# SCH.net
KiCad netlist of a schematic drawn in Altium Designer
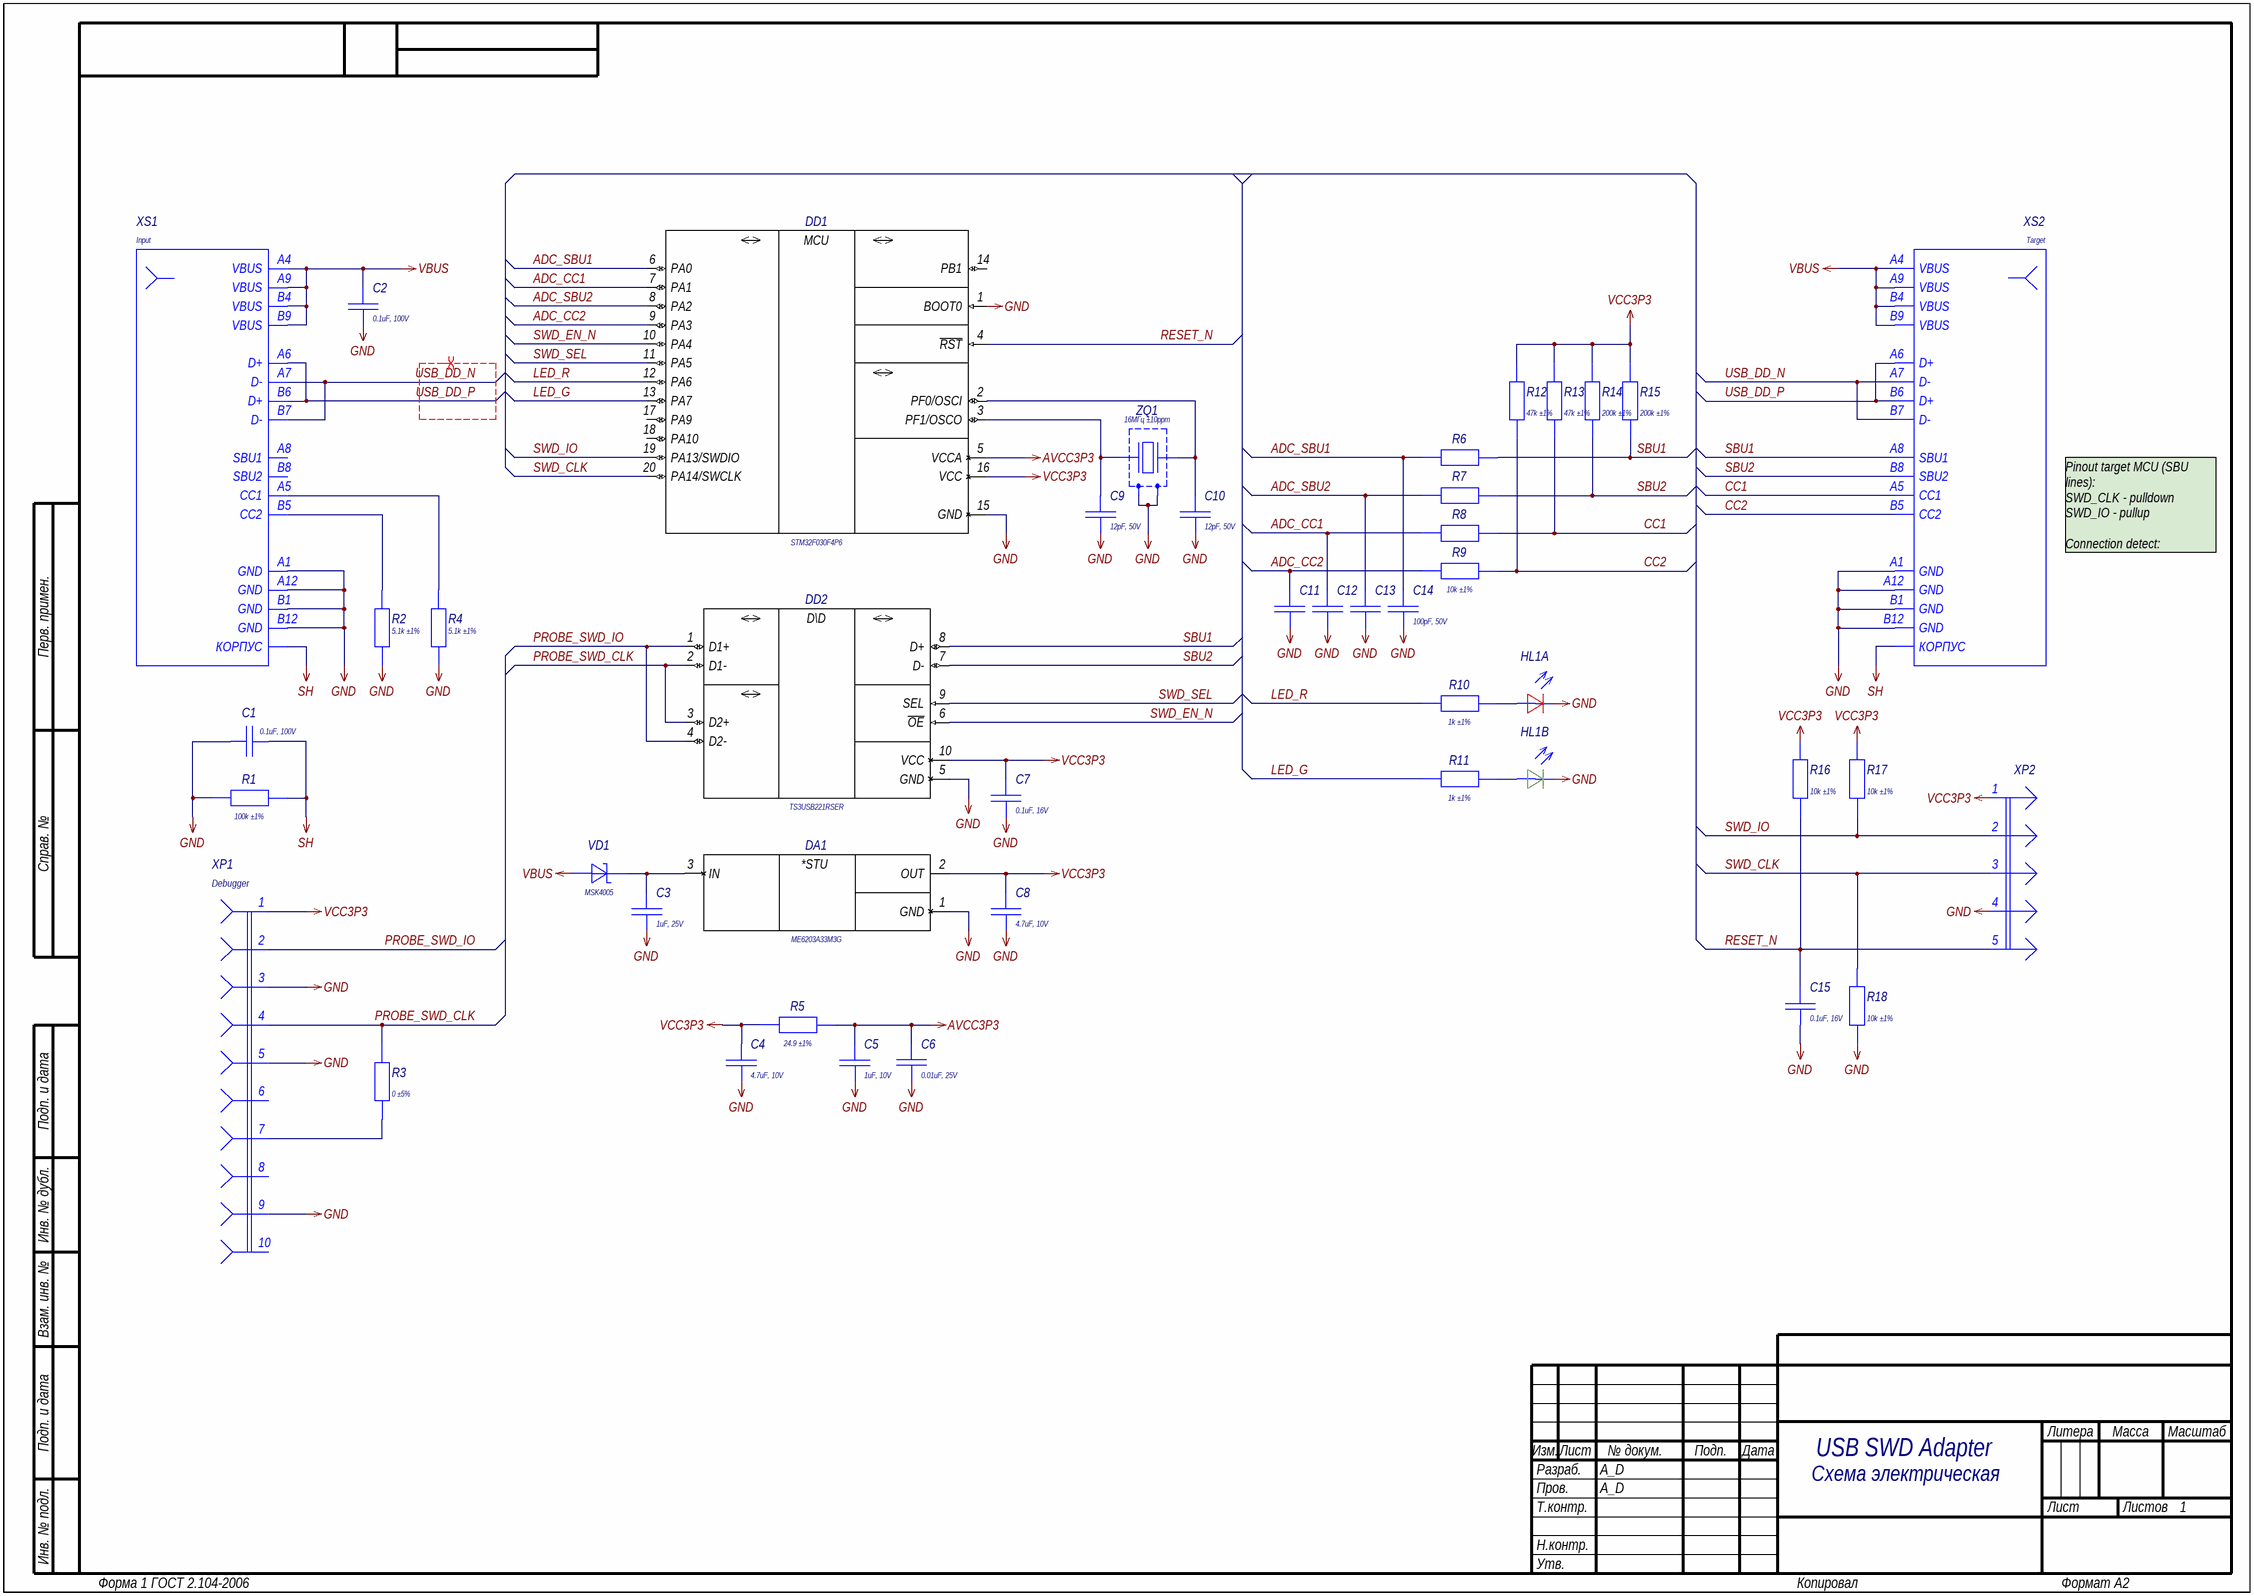
[diagram p0: SCH.SchDoc]

(export (version "E")
  (design (tool "Eeschema 10.0.6"))
  (components
    (comp (ref "C1")
      (value "Capacitor")
      (footprint "C0603_160X080H080_H")
      (fields
        (field (name "PART NUMBER") "GRM188R72A104KA35D")
        (field (name "VOLTAGE") "100V")
        (field (name "TOLERANCE") "±10%")
        (field (name "SCHEMATIC VALUE") "0.1uF, 100V")
      )
      (libsource (lib "ADLib") (part "Capacitor"))
    )
    (comp (ref "C2")
      (value "Capacitor")
      (footprint "C0603_160X080H080_H")
      (fields
        (field (name "PART NUMBER") "GRM188R72A104KA35D")
        (field (name "VOLTAGE") "100V")
        (field (name "TOLERANCE") "±10%")
        (field (name "SCHEMATIC VALUE") "0.1uF, 100V")
      )
      (libsource (lib "ADLib") (part "Capacitor"))
    )
    (comp (ref "C3")
      (value "Capacitor")
      (footprint "C0603_160X080H080_H")
      (fields
        (field (name "PART NUMBER") "GCM188R71E105KA64D")
        (field (name "VOLTAGE") "25V")
        (field (name "TOLERANCE") "±10%")
        (field (name "SCHEMATIC VALUE") "1uF, 25V")
      )
      (libsource (lib "ADLib") (part "Capacitor"))
    )
    (comp (ref "C4")
      (value "Capacitor")
      (footprint "C0402_100X050H050_H")
      (fields
        (field (name "PART NUMBER") "GRM155R61A475MEAAD")
        (field (name "VOLTAGE") "10V")
        (field (name "TOLERANCE") "±20%")
        (field (name "SCHEMATIC VALUE") "4.7uF, 10V")
      )
      (libsource (lib "ADLib") (part "Capacitor"))
    )
    (comp (ref "C5")
      (value "Capacitor")
      (footprint "C0402_100X050H050_H")
      (fields
        (field (name "PART NUMBER") "GRM155C71A105KE11D")
        (field (name "VOLTAGE") "10V")
        (field (name "TOLERANCE") "±10%")
        (field (name "SCHEMATIC VALUE") "1uF, 10V")
      )
      (libsource (lib "ADLib") (part "Capacitor"))
    )
    (comp (ref "C6")
      (value "Capacitor")
      (footprint "C0402_100X050H050_H")
      (fields
        (field (name "PART NUMBER") "GCM155R71E103KA37D")
        (field (name "VOLTAGE") "25V")
        (field (name "TOLERANCE") "±10%")
        (field (name "SCHEMATIC VALUE") "0.01uF, 25V")
      )
      (libsource (lib "ADLib") (part "Capacitor"))
    )
    (comp (ref "C7")
      (value "Capacitor")
      (footprint "C0402_100X050H050_H")
      (fields
        (field (name "PART NUMBER") "GCM155R71C104KA55D")
        (field (name "VOLTAGE") "16V")
        (field (name "TOLERANCE") "±10%")
        (field (name "SCHEMATIC VALUE") "0.1uF, 16V")
      )
      (libsource (lib "ADLib") (part "Capacitor"))
    )
    (comp (ref "C8")
      (value "Capacitor")
      (footprint "C0402_100X050H050_H")
      (fields
        (field (name "PART NUMBER") "GRM155R61A475MEAAD")
        (field (name "VOLTAGE") "10V")
        (field (name "TOLERANCE") "±20%")
        (field (name "SCHEMATIC VALUE") "4.7uF, 10V")
      )
      (libsource (lib "ADLib") (part "Capacitor"))
    )
    (comp (ref "C9")
      (value "Capacitor")
      (footprint "C0402_100X050H050_H")
      (fields
        (field (name "PART NUMBER") "GRM1555C1H120JA01D")
        (field (name "VOLTAGE") "50V")
        (field (name "TOLERANCE") "±5%")
        (field (name "SCHEMATIC VALUE") "12pF, 50V")
      )
      (libsource (lib "ADLib") (part "Capacitor"))
    )
    (comp (ref "C10")
      (value "Capacitor")
      (footprint "C0402_100X050H050_H")
      (fields
        (field (name "PART NUMBER") "GRM1555C1H120JA01D")
        (field (name "VOLTAGE") "50V")
        (field (name "TOLERANCE") "±5%")
        (field (name "SCHEMATIC VALUE") "12pF, 50V")
      )
      (libsource (lib "ADLib") (part "Capacitor"))
    )
    (comp (ref "C11")
      (value "Capacitor")
      (footprint "C0402_100X050H050_H")
      (fields
        (field (name "PART NUMBER") "GCM1555C1H101FA16D")
        (field (name "VOLTAGE") "50V")
        (field (name "TOLERANCE") "±1%")
      )
      (libsource (lib "ADLib") (part "Capacitor"))
    )
    (comp (ref "C12")
      (value "Capacitor")
      (footprint "C0402_100X050H050_H")
      (fields
        (field (name "PART NUMBER") "GCM1555C1H101FA16D")
        (field (name "VOLTAGE") "50V")
        (field (name "TOLERANCE") "±1%")
      )
      (libsource (lib "ADLib") (part "Capacitor"))
    )
    (comp (ref "C13")
      (value "Capacitor")
      (footprint "C0402_100X050H050_H")
      (fields
        (field (name "PART NUMBER") "GCM1555C1H101FA16D")
        (field (name "VOLTAGE") "50V")
        (field (name "TOLERANCE") "±1%")
      )
      (libsource (lib "ADLib") (part "Capacitor"))
    )
    (comp (ref "C14")
      (value "Capacitor")
      (footprint "C0402_100X050H050_H")
      (fields
        (field (name "PART NUMBER") "GCM1555C1H101FA16D")
        (field (name "VOLTAGE") "50V")
        (field (name "TOLERANCE") "±1%")
        (field (name "SCHEMATIC VALUE") "100pF, 50V")
      )
      (libsource (lib "ADLib") (part "Capacitor"))
    )
    (comp (ref "C15")
      (value "Capacitor")
      (footprint "C0402_100X050H050_H")
      (fields
        (field (name "PART NUMBER") "GCM155R71C104KA55D")
        (field (name "VOLTAGE") "16V")
        (field (name "TOLERANCE") "±10%")
        (field (name "SCHEMATIC VALUE") "0.1uF, 16V")
      )
      (libsource (lib "ADLib") (part "Capacitor"))
    )
    (comp (ref "DA1")
      (value "ME6203Axx-Series")
      (footprint "SOT-23_190P290X160X145_N")
      (fields
        (field (name "PART NUMBER") "ME6203A33M3G")
        (field (name "LCSC PART") "C87842")
        (field (name "MANUFACTURER") "Nanjing Micro One Elec")
        (field (name "SCHEMATIC VALUE") "ME6203A33M3G")
      )
      (libsource (lib "ADLib") (part "ME6203Axx-Series"))
    )
    (comp (ref "DD1")
      (value "STM32F030FxPx-Series")
      (footprint "TSSOP-20_065P650X440X120_N")
      (fields
        (field (name "PART NUMBER") "STM32F030F4P6")
        (field (name "LCSC PART") "C32908")
        (field (name "MANUFACTURER") "STMicroelectronics")
        (field (name "SCHEMATIC VALUE") "STM32F030F4P6")
      )
      (libsource (lib "ADLib") (part "STM32F030FxPx-Series"))
    )
    (comp (ref "DD2")
      (value "TS3USB221RSE")
      (footprint "UQFN-10_050P200X150X060_N")
      (fields
        (field (name "PART NUMBER") "TS3USB221RSER")
        (field (name "LCSC PART") "C130085")
        (field (name "MANUFACTURER") "Texas Instruments")
        (field (name "SCHEMATIC VALUE") "TS3USB221RSER")
      )
      (libsource (lib "ADLib") (part "TS3USB221RSE"))
    )
    (comp (ref "HL1")
      (value "Text")
      (footprint "LD3025")
      (fields
        (field (name "PART NUMBER") "XL-3227SURUGC")
        (field (name "LCSC PART") "C965842")
        (field (name "MANUFACTURER") "XINGLIGHT")
        (field (name "PUBLISHER") "Andrew Danich")
      )
      (libsource (lib "ADLib") (part "Led-2-RG-4p"))
    )
    (comp (ref "R1")
      (value "Resistor")
      (footprint "R0402_100X050H035_H")
      (fields
        (field (name "PART NUMBER") "0402WGF1003TCE")
        (field (name "TOLERANCE") "±1%")
        (field (name "MANUFACTURER") "Uniroyal Elec")
        (field (name "SCHEMATIC VALUE") "100k ±1%")
      )
      (libsource (lib "ADLib") (part "Resistor"))
    )
    (comp (ref "R2")
      (value "Resistor")
      (footprint "R0402_100X050H035_H")
      (fields
        (field (name "PART NUMBER") "0402WGF5101TCE")
        (field (name "TOLERANCE") "±1%")
        (field (name "MANUFACTURER") "Uniroyal Elec")
        (field (name "SCHEMATIC VALUE") "5.1k ±1%")
      )
      (libsource (lib "ADLib") (part "Resistor"))
    )
    (comp (ref "R3")
      (value "Resistor")
      (footprint "R0402_100X050H035_H")
      (fields
        (field (name "PART NUMBER") "RC0402JR-070RL")
        (field (name "TOLERANCE") "±5%")
        (field (name "MANUFACTURER") "Yageo")
        (field (name "SCHEMATIC VALUE") "0 ±5%")
      )
      (libsource (lib "ADLib") (part "Resistor"))
    )
    (comp (ref "R4")
      (value "Resistor")
      (footprint "R0402_100X050H035_H")
      (fields
        (field (name "PART NUMBER") "0402WGF5101TCE")
        (field (name "TOLERANCE") "±1%")
        (field (name "MANUFACTURER") "Uniroyal Elec")
        (field (name "SCHEMATIC VALUE") "5.1k ±1%")
      )
      (libsource (lib "ADLib") (part "Resistor"))
    )
    (comp (ref "R5")
      (value "Resistor")
      (footprint "R0402_100X050H035_H")
      (fields
        (field (name "PART NUMBER") "RC0402FR-0724R9L")
        (field (name "TOLERANCE") "±1%")
        (field (name "MANUFACTURER") "Yageo")
        (field (name "SCHEMATIC VALUE") "24.9 ±1%")
      )
      (libsource (lib "ADLib") (part "Resistor"))
    )
    (comp (ref "R6")
      (value "Resistor")
      (footprint "R0402_100X050H035_H")
      (fields
        (field (name "PART NUMBER") "0402WGF1002TCE")
        (field (name "TOLERANCE") "±1%")
        (field (name "MANUFACTURER") "Uniroyal Elec")
      )
      (libsource (lib "ADLib") (part "Resistor"))
    )
    (comp (ref "R7")
      (value "Resistor")
      (footprint "R0402_100X050H035_H")
      (fields
        (field (name "PART NUMBER") "0402WGF1002TCE")
        (field (name "TOLERANCE") "±1%")
        (field (name "MANUFACTURER") "Uniroyal Elec")
      )
      (libsource (lib "ADLib") (part "Resistor"))
    )
    (comp (ref "R8")
      (value "Resistor")
      (footprint "R0402_100X050H035_H")
      (fields
        (field (name "PART NUMBER") "0402WGF1002TCE")
        (field (name "TOLERANCE") "±1%")
        (field (name "MANUFACTURER") "Uniroyal Elec")
      )
      (libsource (lib "ADLib") (part "Resistor"))
    )
    (comp (ref "R9")
      (value "Resistor")
      (footprint "R0402_100X050H035_H")
      (fields
        (field (name "PART NUMBER") "0402WGF1002TCE")
        (field (name "TOLERANCE") "±1%")
        (field (name "MANUFACTURER") "Uniroyal Elec")
        (field (name "SCHEMATIC VALUE") "10k ±1%")
      )
      (libsource (lib "ADLib") (part "Resistor"))
    )
    (comp (ref "R10")
      (value "Resistor")
      (footprint "R0402_100X050H035_H")
      (fields
        (field (name "PART NUMBER") "0402WGF1001TCE")
        (field (name "TOLERANCE") "±1%")
        (field (name "MANUFACTURER") "Uniroyal Elec")
        (field (name "SCHEMATIC VALUE") "1k ±1%")
      )
      (libsource (lib "ADLib") (part "Resistor"))
    )
    (comp (ref "R11")
      (value "Resistor")
      (footprint "R0402_100X050H035_H")
      (fields
        (field (name "PART NUMBER") "0402WGF1001TCE")
        (field (name "TOLERANCE") "±1%")
        (field (name "MANUFACTURER") "Uniroyal Elec")
        (field (name "SCHEMATIC VALUE") "1k ±1%")
      )
      (libsource (lib "ADLib") (part "Resistor"))
    )
    (comp (ref "R12")
      (value "Resistor")
      (footprint "R0402_100X050H035_H")
      (fields
        (field (name "PART NUMBER") "0402WGF4702TCE")
        (field (name "TOLERANCE") "±1%")
        (field (name "MANUFACTURER") "Uniroyal Elec")
        (field (name "SCHEMATIC VALUE") "47k ±1%")
      )
      (libsource (lib "ADLib") (part "Resistor"))
    )
    (comp (ref "R13")
      (value "Resistor")
      (footprint "R0402_100X050H035_H")
      (fields
        (field (name "PART NUMBER") "0402WGF4702TCE")
        (field (name "TOLERANCE") "±1%")
        (field (name "MANUFACTURER") "Uniroyal Elec")
        (field (name "SCHEMATIC VALUE") "47k ±1%")
      )
      (libsource (lib "ADLib") (part "Resistor"))
    )
    (comp (ref "R14")
      (value "Resistor")
      (footprint "R0402_100X050H035_H")
      (fields
        (field (name "PART NUMBER") "0402WGF2003TCE")
        (field (name "TOLERANCE") "±1%")
        (field (name "MANUFACTURER") "Uniroyal Elec")
        (field (name "SCHEMATIC VALUE") "200k ±1%")
      )
      (libsource (lib "ADLib") (part "Resistor"))
    )
    (comp (ref "R15")
      (value "Resistor")
      (footprint "R0402_100X050H035_H")
      (fields
        (field (name "PART NUMBER") "0402WGF2003TCE")
        (field (name "TOLERANCE") "±1%")
        (field (name "MANUFACTURER") "Uniroyal Elec")
        (field (name "SCHEMATIC VALUE") "200k ±1%")
      )
      (libsource (lib "ADLib") (part "Resistor"))
    )
    (comp (ref "R16")
      (value "Resistor")
      (footprint "R0402_100X050H035_H")
      (fields
        (field (name "PART NUMBER") "0402WGF1002TCE")
        (field (name "TOLERANCE") "±1%")
        (field (name "MANUFACTURER") "Uniroyal Elec")
        (field (name "SCHEMATIC VALUE") "10k ±1%")
      )
      (libsource (lib "ADLib") (part "Resistor"))
    )
    (comp (ref "R17")
      (value "Resistor")
      (footprint "R0402_100X050H035_H")
      (fields
        (field (name "PART NUMBER") "0402WGF1002TCE")
        (field (name "TOLERANCE") "±1%")
        (field (name "MANUFACTURER") "Uniroyal Elec")
        (field (name "SCHEMATIC VALUE") "10k ±1%")
      )
      (libsource (lib "ADLib") (part "Resistor"))
    )
    (comp (ref "R18")
      (value "Resistor")
      (footprint "R0402_100X050H035_H")
      (fields
        (field (name "PART NUMBER") "0402WGF1002TCE")
        (field (name "TOLERANCE") "±1%")
        (field (name "MANUFACTURER") "Uniroyal Elec")
        (field (name "SCHEMATIC VALUE") "10k ±1%")
      )
      (libsource (lib "ADLib") (part "Resistor"))
    )
    (comp (ref "VD1")
      (value "Schottky")
      (footprint "SOD-523")
      (fields
        (field (name "PART NUMBER") "MSK4005")
        (field (name "LCSC PART") "C345957")
        (field (name "MANUFACTURER") "Shikues")
        (field (name "SCHEMATIC VALUE") "MSK4005")
      )
      (libsource (lib "ADLib") (part "Schottky"))
    )
    (comp (ref "XP1")
      (value "Debugger")
      (footprint "PBD-10")
      (fields (field (name "PART NUMBER") "PBD-10"))
      (libsource (lib "ADLib") (part "Con-10-F"))
    )
    (comp (ref "XP2")
      (value "SWD")
      (footprint "PLS-5")
      (fields (field (name "PART NUMBER") "PLS-5"))
      (libsource (lib "ADLib") (part "Con-5-M"))
    )
    (comp (ref "XS1")
      (value "Input")
      (footprint "U262-161N-4BVC11")
      (fields
        (field (name "PART NUMBER") "U262-161N-4BVC11")
        (field (name "LCSC PART") "C319148")
        (field (name "MANUFACTURER") "XKB Enterprise")
      )
      (libsource (lib "") (part "Con-USB_C-F-16P_1"))
    )
    (comp (ref "XS2")
      (value "Target")
      (footprint "U262-161N-4BVC11")
      (fields
        (field (name "PART NUMBER") "U262-161N-4BVC11")
        (field (name "LCSC PART") "C319148")
        (field (name "MANUFACTURER") "XKB Enterprise")
      )
      (libsource (lib "ADLib") (part "Con-USB_C-F-16P"))
    )
    (comp (ref "ZQ1")
      (value "Crystal-1_3p_S")
      (footprint "SMD 3.2x2.5mm")
      (fields
        (field (name "PART NUMBER") "X322516MOB4SI")
        (field (name "LCSC PART") "C12668")
        (field (name "MANUFACTURER") "Yangxing Tech")
        (field (name "SCHEMATIC VALUE") "16МГц ±10ppm")
      )
      (libsource (lib "ADLib") (part "Crystal-1_3p_S"))
    )
  )
  (nets
    (net (code "1") (name "/ADC_CC1") (class "Default")
      (node (ref "C12") (pin "2") (pinfunction "2_2") (pintype "passive"))
      (node (ref "DD1") (pin "7") (pinfunction "PA1_7") (pintype "bidirectional"))
      (node (ref "R8") (pin "2") (pinfunction "2_2") (pintype "passive"))
    )
    (net (code "2") (name "/ADC_CC2") (class "Default")
      (node (ref "C11") (pin "2") (pinfunction "2_2") (pintype "passive"))
      (node (ref "DD1") (pin "9") (pinfunction "PA3_9") (pintype "bidirectional"))
      (node (ref "R9") (pin "2") (pinfunction "2_2") (pintype "passive"))
    )
    (net (code "3") (name "/ADC_SBU1") (class "Default")
      (node (ref "C14") (pin "2") (pinfunction "2_2") (pintype "passive"))
      (node (ref "DD1") (pin "6") (pinfunction "PA0_6") (pintype "bidirectional"))
      (node (ref "R6") (pin "2") (pinfunction "2_2") (pintype "passive"))
    )
    (net (code "4") (name "/ADC_SBU2") (class "Default")
      (node (ref "C13") (pin "2") (pinfunction "2_2") (pintype "passive"))
      (node (ref "DD1") (pin "8") (pinfunction "PA2_8") (pintype "bidirectional"))
      (node (ref "R7") (pin "2") (pinfunction "2_2") (pintype "passive"))
    )
    (net (code "5") (name "/CC1") (class "Default")
      (node (ref "R13") (pin "1") (pinfunction "1_1") (pintype "passive"))
      (node (ref "R8") (pin "1") (pinfunction "1_1") (pintype "passive"))
      (node (ref "XS2") (pin "A5") (pinfunction "CC1_A5") (pintype "passive"))
    )
    (net (code "6") (name "/CC2") (class "Default")
      (node (ref "R12") (pin "1") (pinfunction "1_1") (pintype "passive"))
      (node (ref "R9") (pin "1") (pinfunction "1_1") (pintype "passive"))
      (node (ref "XS2") (pin "B5") (pinfunction "CC2_B5") (pintype "passive"))
    )
    (net (code "7") (name "/LED_G") (class "Default")
      (node (ref "DD1") (pin "13") (pinfunction "PA7_13") (pintype "bidirectional"))
      (node (ref "R11") (pin "2") (pinfunction "2_2") (pintype "passive"))
    )
    (net (code "8") (name "/LED_R") (class "Default")
      (node (ref "DD1") (pin "12") (pinfunction "PA6_12") (pintype "bidirectional"))
      (node (ref "R10") (pin "2") (pinfunction "2_2") (pintype "passive"))
    )
    (net (code "9") (name "/PROBE_SWD_CLK") (class "Default")
      (node (ref "DD2") (pin "2") (pinfunction "D1-_2") (pintype "bidirectional"))
      (node (ref "DD2") (pin "3") (pinfunction "D2+_3") (pintype "bidirectional"))
      (node (ref "R3") (pin "1") (pinfunction "1_1") (pintype "passive"))
      (node (ref "XP1") (pin "4") (pintype "passive"))
    )
    (net (code "10") (name "/PROBE_SWD_IO") (class "Default")
      (node (ref "DD2") (pin "1") (pinfunction "D1+_1") (pintype "bidirectional"))
      (node (ref "DD2") (pin "4") (pinfunction "D2-_4") (pintype "bidirectional"))
      (node (ref "XP1") (pin "2") (pintype "passive"))
    )
    (net (code "11") (name "/RESET_N") (class "Default")
      (node (ref "C15") (pin "2") (pinfunction "2_2") (pintype "passive"))
      (node (ref "DD1") (pin "4") (pinfunction "~{RST}_4") (pintype "input"))
      (node (ref "R16") (pin "2") (pinfunction "2_2") (pintype "passive"))
      (node (ref "XP2") (pin "5") (pintype "passive"))
    )
    (net (code "12") (name "/SBU1") (class "Default")
      (node (ref "DD2") (pin "8") (pinfunction "D+_8") (pintype "bidirectional"))
      (node (ref "R15") (pin "1") (pinfunction "1_1") (pintype "passive"))
      (node (ref "R6") (pin "1") (pinfunction "1_1") (pintype "passive"))
      (node (ref "XS2") (pin "A8") (pinfunction "SBU1_A8") (pintype "passive"))
    )
    (net (code "13") (name "/SBU2") (class "Default")
      (node (ref "DD2") (pin "7") (pinfunction "D-_7") (pintype "bidirectional"))
      (node (ref "R14") (pin "1") (pinfunction "1_1") (pintype "passive"))
      (node (ref "R7") (pin "1") (pinfunction "1_1") (pintype "passive"))
      (node (ref "XS2") (pin "B8") (pinfunction "SBU2_B8") (pintype "passive"))
    )
    (net (code "14") (name "/SWD_CLK") (class "Default")
      (node (ref "DD1") (pin "20") (pinfunction "PA14/SWCLK_20") (pintype "bidirectional"))
      (node (ref "R18") (pin "1") (pinfunction "1_1") (pintype "passive"))
      (node (ref "XP2") (pin "3") (pintype "passive"))
    )
    (net (code "15") (name "/SWD_EN_N") (class "Default")
      (node (ref "DD1") (pin "10") (pinfunction "PA4_10") (pintype "bidirectional"))
      (node (ref "DD2") (pin "6") (pinfunction "~{OE}_6") (pintype "input"))
    )
    (net (code "16") (name "/SWD_IO") (class "Default")
      (node (ref "DD1") (pin "19") (pinfunction "PA13/SWDIO_19") (pintype "bidirectional"))
      (node (ref "R17") (pin "2") (pinfunction "2_2") (pintype "passive"))
      (node (ref "XP2") (pin "2") (pintype "passive"))
    )
    (net (code "17") (name "/SWD_SEL") (class "Default")
      (node (ref "DD1") (pin "11") (pinfunction "PA5_11") (pintype "bidirectional"))
      (node (ref "DD2") (pin "9") (pinfunction "SEL_9") (pintype "input"))
    )
    (net (code "18") (name "/USB_DD_N") (class "Default")
      (node (ref "XS1") (pin "A7") (pinfunction "D-_A7") (pintype "passive"))
      (node (ref "XS1") (pin "B7") (pinfunction "D-_B7") (pintype "passive"))
      (node (ref "XS2") (pin "A7") (pinfunction "D-_A7") (pintype "passive"))
      (node (ref "XS2") (pin "B7") (pinfunction "D-_B7") (pintype "passive"))
    )
    (net (code "19") (name "/USB_DD_P") (class "Default")
      (node (ref "XS1") (pin "A6") (pinfunction "D+_A6") (pintype "passive"))
      (node (ref "XS1") (pin "B6") (pinfunction "D+_B6") (pintype "passive"))
      (node (ref "XS2") (pin "A6") (pinfunction "D+_A6") (pintype "passive"))
      (node (ref "XS2") (pin "B6") (pinfunction "D+_B6") (pintype "passive"))
    )
    (net (code "20") (name "AVCC3P3") (class "Default")
      (node (ref "C5") (pin "2") (pinfunction "2_2") (pintype "passive"))
      (node (ref "C6") (pin "1") (pinfunction "1_1") (pintype "passive"))
      (node (ref "DD1") (pin "5") (pinfunction "VCCA_5") (pintype "power_in"))
      (node (ref "R5") (pin "1") (pinfunction "1_1") (pintype "passive"))
    )
    (net (code "21") (name "GND") (class "Default")
      (node (ref "C1") (pin "2") (pinfunction "2_2") (pintype "passive"))
      (node (ref "C10") (pin "1") (pinfunction "1_1") (pintype "passive"))
      (node (ref "C11") (pin "1") (pinfunction "1_1") (pintype "passive"))
      (node (ref "C12") (pin "1") (pinfunction "1_1") (pintype "passive"))
      (node (ref "C13") (pin "1") (pinfunction "1_1") (pintype "passive"))
      (node (ref "C14") (pin "1") (pinfunction "1_1") (pintype "passive"))
      (node (ref "C15") (pin "1") (pinfunction "1_1") (pintype "passive"))
      (node (ref "C2") (pin "1") (pinfunction "1_1") (pintype "passive"))
      (node (ref "C3") (pin "1") (pinfunction "1_1") (pintype "passive"))
      (node (ref "C4") (pin "1") (pinfunction "1_1") (pintype "passive"))
      (node (ref "C5") (pin "1") (pinfunction "1_1") (pintype "passive"))
      (node (ref "C6") (pin "2") (pinfunction "2_2") (pintype "passive"))
      (node (ref "C7") (pin "1") (pinfunction "1_1") (pintype "passive"))
      (node (ref "C8") (pin "1") (pinfunction "1_1") (pintype "passive"))
      (node (ref "C9") (pin "1") (pinfunction "1_1") (pintype "passive"))
      (node (ref "DA1") (pin "1") (pinfunction "GND_1") (pintype "power_in"))
      (node (ref "DD1") (pin "1") (pinfunction "BOOT0_1") (pintype "input"))
      (node (ref "DD1") (pin "15") (pinfunction "GND_15") (pintype "power_in"))
      (node (ref "DD2") (pin "5") (pinfunction "GND_5") (pintype "power_in"))
      (node (ref "HL1") (pin "2") (pintype "passive"))
      (node (ref "HL1") (pin "4") (pintype "passive"))
      (node (ref "R1") (pin "2") (pinfunction "2_2") (pintype "passive"))
      (node (ref "R18") (pin "2") (pinfunction "2_2") (pintype "passive"))
      (node (ref "R2") (pin "1") (pinfunction "1_1") (pintype "passive"))
      (node (ref "R4") (pin "1") (pinfunction "1_1") (pintype "passive"))
      (node (ref "XP1") (pin "3") (pintype "passive"))
      (node (ref "XP1") (pin "5") (pintype "passive"))
      (node (ref "XP1") (pin "9") (pintype "passive"))
      (node (ref "XP2") (pin "4") (pintype "passive"))
      (node (ref "XS1") (pin "A1") (pinfunction "GND_A1") (pintype "passive"))
      (node (ref "XS1") (pin "A12") (pinfunction "GND_A12") (pintype "passive"))
      (node (ref "XS1") (pin "B1") (pinfunction "GND_B1") (pintype "passive"))
      (node (ref "XS1") (pin "B12") (pinfunction "GND_B12") (pintype "passive"))
      (node (ref "XS2") (pin "A1") (pinfunction "GND_A1") (pintype "passive"))
      (node (ref "XS2") (pin "A12") (pinfunction "GND_A12") (pintype "passive"))
      (node (ref "XS2") (pin "B1") (pinfunction "GND_B1") (pintype "passive"))
      (node (ref "XS2") (pin "B12") (pinfunction "GND_B12") (pintype "passive"))
      (node (ref "ZQ1") (pin "2") (pinfunction "2_2") (pintype "passive"))
      (node (ref "ZQ1") (pin "4") (pinfunction "4_4") (pintype "passive"))
    )
    (net (code "22") (name "Net-(DA1-IN)") (class "Default")
      (node (ref "C3") (pin "2") (pinfunction "2_2") (pintype "passive"))
      (node (ref "DA1") (pin "3") (pinfunction "IN_3") (pintype "power_in"))
      (node (ref "VD1") (pin "2") (pinfunction "К_2") (pintype "passive"))
    )
    (net (code "23") (name "Net-(DD1-PF0{slash}OSCI)") (class "Default")
      (node (ref "C10") (pin "2") (pinfunction "2_2") (pintype "passive"))
      (node (ref "DD1") (pin "2") (pinfunction "PF0/OSCI_2") (pintype "bidirectional"))
      (node (ref "ZQ1") (pin "3") (pinfunction "3_3") (pintype "passive"))
    )
    (net (code "24") (name "Net-(DD1-PF1{slash}OSCO)") (class "Default")
      (node (ref "C9") (pin "2") (pinfunction "2_2") (pintype "passive"))
      (node (ref "DD1") (pin "3") (pinfunction "PF1/OSCO_3") (pintype "bidirectional"))
      (node (ref "ZQ1") (pin "1") (pinfunction "1_1") (pintype "passive"))
    )
    (net (code "25") (name "Net-(HL1-Pad1)") (class "Default")
      (node (ref "HL1") (pin "1") (pintype "passive"))
      (node (ref "R10") (pin "1") (pinfunction "1_1") (pintype "passive"))
    )
    (net (code "26") (name "Net-(HL1-Pad3)") (class "Default")
      (node (ref "HL1") (pin "3") (pintype "passive"))
      (node (ref "R11") (pin "1") (pinfunction "1_1") (pintype "passive"))
    )
    (net (code "27") (name "Net-(R3-Pad2)") (class "Default")
      (node (ref "R3") (pin "2") (pinfunction "2_2") (pintype "passive"))
      (node (ref "XP1") (pin "7") (pintype "passive"))
    )
    (net (code "28") (name "Net-(XS1-CC1)") (class "Default")
      (node (ref "R4") (pin "2") (pinfunction "2_2") (pintype "passive"))
      (node (ref "XS1") (pin "A5") (pinfunction "CC1_A5") (pintype "passive"))
    )
    (net (code "29") (name "Net-(XS1-CC2)") (class "Default")
      (node (ref "R2") (pin "2") (pinfunction "2_2") (pintype "passive"))
      (node (ref "XS1") (pin "B5") (pinfunction "CC2_B5") (pintype "passive"))
    )
    (net (code "30") (name "SH") (class "Default")
      (node (ref "C1") (pin "1") (pinfunction "1_1") (pintype "passive"))
      (node (ref "R1") (pin "1") (pinfunction "1_1") (pintype "passive"))
      (node (ref "XS1") (pin "SH") (pinfunction "КОРПУС_SH") (pintype "passive"))
      (node (ref "XS2") (pin "SH") (pinfunction "КОРПУС_SH") (pintype "passive"))
    )
    (net (code "31") (name "VBUS") (class "Default")
      (node (ref "C2") (pin "2") (pinfunction "2_2") (pintype "passive"))
      (node (ref "VD1") (pin "1") (pinfunction "А_1") (pintype "passive"))
      (node (ref "XS1") (pin "A4") (pinfunction "VBUS_A4") (pintype "passive"))
      (node (ref "XS1") (pin "A9") (pinfunction "VBUS_A9") (pintype "passive"))
      (node (ref "XS1") (pin "B4") (pinfunction "VBUS_B4") (pintype "passive"))
      (node (ref "XS1") (pin "B9") (pinfunction "VBUS_B9") (pintype "passive"))
      (node (ref "XS2") (pin "A4") (pinfunction "VBUS_A4") (pintype "passive"))
      (node (ref "XS2") (pin "A9") (pinfunction "VBUS_A9") (pintype "passive"))
      (node (ref "XS2") (pin "B4") (pinfunction "VBUS_B4") (pintype "passive"))
      (node (ref "XS2") (pin "B9") (pinfunction "VBUS_B9") (pintype "passive"))
    )
    (net (code "32") (name "VCC3P3") (class "Default")
      (node (ref "C4") (pin "2") (pinfunction "2_2") (pintype "passive"))
      (node (ref "C7") (pin "2") (pinfunction "2_2") (pintype "passive"))
      (node (ref "C8") (pin "2") (pinfunction "2_2") (pintype "passive"))
      (node (ref "DA1") (pin "2") (pinfunction "OUT_2") (pintype "power_in"))
      (node (ref "DD1") (pin "16") (pinfunction "VCC_16") (pintype "power_in"))
      (node (ref "DD2") (pin "10") (pinfunction "VCC_10") (pintype "power_in"))
      (node (ref "R12") (pin "2") (pinfunction "2_2") (pintype "passive"))
      (node (ref "R13") (pin "2") (pinfunction "2_2") (pintype "passive"))
      (node (ref "R14") (pin "2") (pinfunction "2_2") (pintype "passive"))
      (node (ref "R15") (pin "2") (pinfunction "2_2") (pintype "passive"))
      (node (ref "R16") (pin "1") (pinfunction "1_1") (pintype "passive"))
      (node (ref "R17") (pin "1") (pinfunction "1_1") (pintype "passive"))
      (node (ref "R5") (pin "2") (pinfunction "2_2") (pintype "passive"))
      (node (ref "XP1") (pin "1") (pintype "passive"))
      (node (ref "XP2") (pin "1") (pintype "passive"))
    )
    (net (code "33") (name "unconnected-(DD1-PA9-Pad17)") (class "Default")
      (node (ref "DD1") (pin "17") (pinfunction "PA9_17") (pintype "bidirectional"))
    )
    (net (code "34") (name "unconnected-(DD1-PA10-Pad18)") (class "Default")
      (node (ref "DD1") (pin "18") (pinfunction "PA10_18") (pintype "bidirectional"))
    )
    (net (code "35") (name "unconnected-(DD1-PB1-Pad14)") (class "Default")
      (node (ref "DD1") (pin "14") (pinfunction "PB1_14") (pintype "bidirectional"))
    )
    (net (code "36") (name "unconnected-(XP1-Pad6)") (class "Default")
      (node (ref "XP1") (pin "6") (pintype "passive"))
    )
    (net (code "37") (name "unconnected-(XP1-Pad8)") (class "Default")
      (node (ref "XP1") (pin "8") (pintype "passive"))
    )
    (net (code "38") (name "unconnected-(XP1-Pad10)") (class "Default")
      (node (ref "XP1") (pin "10") (pintype "passive"))
    )
    (net (code "39") (name "unconnected-(XS1-SBU1-PadA8)") (class "Default")
      (node (ref "XS1") (pin "A8") (pinfunction "SBU1_A8") (pintype "passive"))
    )
    (net (code "40") (name "unconnected-(XS1-SBU2-PadB8)") (class "Default")
      (node (ref "XS1") (pin "B8") (pinfunction "SBU2_B8") (pintype "passive"))
    )
  )
)
